# Holder_Accu_Simetric.net
KiCad netlist of a schematic drawn in Altium Designer
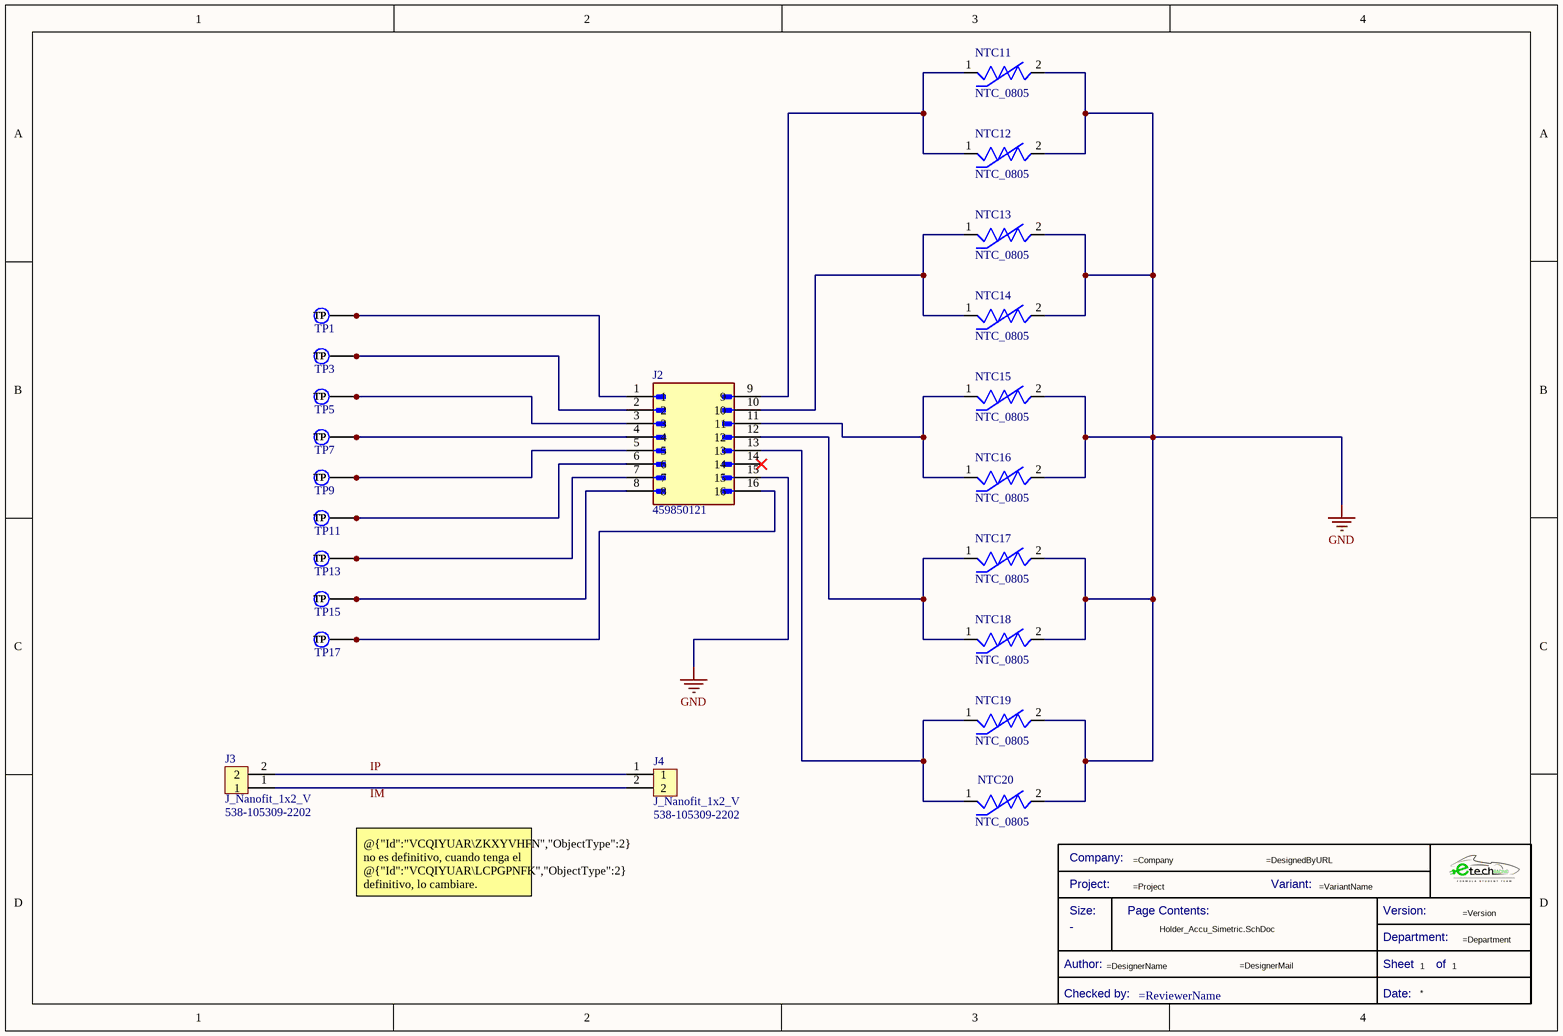
[diagram p0: Holder_Accu_Simetric.SchDoc]

(export (version "E")
  (design (tool "Eeschema 10.0.6"))
  (components
    (comp (ref "*")
      (value "Title Block_template")
      (description "Standard Title Block")
      (fields
        (field (name "SIZE") "-")
        (field (name ".CREATOR") "GP")
        (field (name ".PCBCHECK") "GP")
        (field (name ".SCHCHECK") "GP")
      )
      (libsource (lib "e-Tech_Racing") (part "Title Block_template"))
    )
    (comp (ref "J2")
      (value "459850121")
      (footprint "MOLEX_459850121")
      (libsource (lib "459850121") (part "459850121"))
    )
    (comp (ref "J3")
      (value "J_Nanofit_1x2_V")
      (footprint "J_NanoFit_1X2_V")
      (fields
        (field (name "MANUFACTURER") "Molex")
        (field (name "MANUFACTURER PART NUMBER") "1053092202")
        (field (name "SUPPLIER PART NUMBER 1") "538-105309-2202")
      )
      (libsource (lib "") (part "J_Nanofit_1x2_V_1"))
    )
    (comp (ref "J4")
      (value "J_Nanofit_1x2_V")
      (footprint "J_NanoFit_1X2_V")
      (fields
        (field (name "MANUFACTURER") "Molex")
        (field (name "MANUFACTURER PART NUMBER") "1053092202")
        (field (name "SUPPLIER PART NUMBER 1") "538-105309-2202")
      )
      (libsource (lib "Electromechanical") (part "J_Nanofit_1x2_V"))
    )
    (comp (ref "NTC11")
      (value "NTC_0805")
      (footprint "NTC_0805")
      (description "NTC Thermistor 10k 0805 (2012 Metric)")
      (fields (field (name "MF") "TDK Corporation") (field (name "MP") "NTCG203NH103JTDS"))
      (libsource (lib "yo") (part "NTC_0805"))
    )
    (comp (ref "NTC12")
      (value "NTC_0805")
      (footprint "NTC_0805")
      (description "NTC Thermistor 10k 0805 (2012 Metric)")
      (fields (field (name "MF") "TDK Corporation") (field (name "MP") "NTCG203NH103JTDS"))
      (libsource (lib "yo") (part "NTC_0805"))
    )
    (comp (ref "NTC13")
      (value "NTC_0805")
      (footprint "NTC_0805")
      (description "NTC Thermistor 10k 0805 (2012 Metric)")
      (fields (field (name "MF") "TDK Corporation") (field (name "MP") "NTCG203NH103JTDS"))
      (libsource (lib "yo") (part "NTC_0805"))
    )
    (comp (ref "NTC14")
      (value "NTC_0805")
      (footprint "NTC_0805")
      (description "NTC Thermistor 10k 0805 (2012 Metric)")
      (fields (field (name "MF") "TDK Corporation") (field (name "MP") "NTCG203NH103JTDS"))
      (libsource (lib "yo") (part "NTC_0805"))
    )
    (comp (ref "NTC15")
      (value "NTC_0805")
      (footprint "NTC_0805")
      (description "NTC Thermistor 10k 0805 (2012 Metric)")
      (fields (field (name "MF") "TDK Corporation") (field (name "MP") "NTCG203NH103JTDS"))
      (libsource (lib "yo") (part "NTC_0805"))
    )
    (comp (ref "NTC16")
      (value "NTC_0805")
      (footprint "NTC_0805")
      (description "NTC Thermistor 10k 0805 (2012 Metric)")
      (fields (field (name "MF") "TDK Corporation") (field (name "MP") "NTCG203NH103JTDS"))
      (libsource (lib "yo") (part "NTC_0805"))
    )
    (comp (ref "NTC17")
      (value "NTC_0805")
      (footprint "NTC_0805")
      (description "NTC Thermistor 10k 0805 (2012 Metric)")
      (fields (field (name "MF") "TDK Corporation") (field (name "MP") "NTCG203NH103JTDS"))
      (libsource (lib "yo") (part "NTC_0805"))
    )
    (comp (ref "NTC18")
      (value "NTC_0805")
      (footprint "NTC_0805")
      (description "NTC Thermistor 10k 0805 (2012 Metric)")
      (fields (field (name "MF") "TDK Corporation") (field (name "MP") "NTCG203NH103JTDS"))
      (libsource (lib "yo") (part "NTC_0805"))
    )
    (comp (ref "NTC19")
      (value "NTC_0805")
      (footprint "NTC_0805")
      (description "NTC Thermistor 10k 0805 (2012 Metric)")
      (fields (field (name "MF") "TDK Corporation") (field (name "MP") "NTCG203NH103JTDS"))
      (libsource (lib "yo") (part "NTC_0805"))
    )
    (comp (ref "NTC20")
      (value "NTC_0805")
      (footprint "NTC_0805")
      (description "NTC Thermistor 10k 0805 (2012 Metric)")
      (fields (field (name "MF") "TDK Corporation") (field (name "MP") "NTCG203NH103JTDS"))
      (libsource (lib "yo") (part "NTC_0805"))
    )
    (comp (ref "TP1")
      (value "Test Point")
      (footprint "TESTPOINT_WIDE")
      (description "TestPoint 5x5mm")
      (libsource (lib "e-Tech_Racing") (part "TestPoint_Wide"))
    )
    (comp (ref "TP3")
      (value "Test Point")
      (footprint "TESTPOINT_WIDE")
      (description "TestPoint 5x5mm")
      (libsource (lib "e-Tech_Racing") (part "TestPoint_Wide"))
    )
    (comp (ref "TP5")
      (value "Test Point")
      (footprint "TESTPOINT_WIDE")
      (description "TestPoint 5x5mm")
      (libsource (lib "e-Tech_Racing") (part "TestPoint_Wide"))
    )
    (comp (ref "TP7")
      (value "Test Point")
      (footprint "TESTPOINT_WIDE")
      (description "TestPoint 5x5mm")
      (libsource (lib "e-Tech_Racing") (part "TestPoint_Wide"))
    )
    (comp (ref "TP9")
      (value "Test Point")
      (footprint "TESTPOINT_WIDE")
      (description "TestPoint 5x5mm")
      (libsource (lib "e-Tech_Racing") (part "TestPoint_Wide"))
    )
    (comp (ref "TP11")
      (value "Test Point")
      (footprint "TESTPOINT_WIDE")
      (description "TestPoint 5x5mm")
      (libsource (lib "e-Tech_Racing") (part "TestPoint_Wide"))
    )
    (comp (ref "TP13")
      (value "Test Point")
      (footprint "TESTPOINT_WIDE")
      (description "TestPoint 5x5mm")
      (libsource (lib "e-Tech_Racing") (part "TestPoint_Wide"))
    )
    (comp (ref "TP15")
      (value "Test Point")
      (footprint "TESTPOINT_WIDE")
      (description "TestPoint 5x5mm")
      (libsource (lib "e-Tech_Racing") (part "TestPoint_Wide"))
    )
    (comp (ref "TP17")
      (value "Test Point")
      (footprint "TESTPOINT_WIDE")
      (description "TestPoint 5x5mm")
      (libsource (lib "e-Tech_Racing") (part "TestPoint_Wide"))
    )
  )
  (nets
    (net (code "2") (name "/IP") (class "Default")
      (node (ref "J3") (pin "2") (pinfunction "2_2") (pintype "passive"))
      (node (ref "J4") (pin "1") (pinfunction "1_1") (pintype "passive"))
    )
    (net (code "3") (name "GND") (class "Default")
      (node (ref "J2") (pin "15") (pinfunction "15_15") (pintype "passive"))
      (node (ref "NTC11") (pin "2") (pinfunction "2_2") (pintype "passive"))
      (node (ref "NTC12") (pin "2") (pinfunction "2_2") (pintype "passive"))
      (node (ref "NTC13") (pin "2") (pinfunction "2_2") (pintype "passive"))
      (node (ref "NTC14") (pin "2") (pinfunction "2_2") (pintype "passive"))
      (node (ref "NTC15") (pin "2") (pinfunction "2_2") (pintype "passive"))
      (node (ref "NTC16") (pin "2") (pinfunction "2_2") (pintype "passive"))
      (node (ref "NTC17") (pin "2") (pinfunction "2_2") (pintype "passive"))
      (node (ref "NTC18") (pin "2") (pinfunction "2_2") (pintype "passive"))
      (node (ref "NTC19") (pin "2") (pinfunction "2_2") (pintype "passive"))
      (node (ref "NTC20") (pin "2") (pinfunction "2_2") (pintype "passive"))
    )
    (net (code "4") (name "Net-(J2-Pad9)") (class "Default")
      (node (ref "J2") (pin "9") (pinfunction "9_9") (pintype "passive"))
      (node (ref "NTC11") (pin "1") (pinfunction "1_1") (pintype "passive"))
      (node (ref "NTC12") (pin "1") (pinfunction "1_1") (pintype "passive"))
    )
    (net (code "5") (name "Net-(J2-Pad10)") (class "Default")
      (node (ref "J2") (pin "10") (pinfunction "10_10") (pintype "passive"))
      (node (ref "NTC13") (pin "1") (pinfunction "1_1") (pintype "passive"))
      (node (ref "NTC14") (pin "1") (pinfunction "1_1") (pintype "passive"))
    )
    (net (code "6") (name "Net-(J2-Pad11)") (class "Default")
      (node (ref "J2") (pin "11") (pinfunction "11_11") (pintype "passive"))
      (node (ref "NTC15") (pin "1") (pinfunction "1_1") (pintype "passive"))
      (node (ref "NTC16") (pin "1") (pinfunction "1_1") (pintype "passive"))
    )
    (net (code "7") (name "Net-(J2-Pad12)") (class "Default")
      (node (ref "J2") (pin "12") (pinfunction "12_12") (pintype "passive"))
      (node (ref "NTC17") (pin "1") (pinfunction "1_1") (pintype "passive"))
      (node (ref "NTC18") (pin "1") (pinfunction "1_1") (pintype "passive"))
    )
    (net (code "8") (name "Net-(J2-Pad13)") (class "Default")
      (node (ref "J2") (pin "13") (pinfunction "13_13") (pintype "passive"))
      (node (ref "NTC19") (pin "1") (pinfunction "1_1") (pintype "passive"))
      (node (ref "NTC20") (pin "1") (pinfunction "1_1") (pintype "passive"))
    )
    (net (code "9") (name "Net-(J3-Pad1)") (class "Default")
      (node (ref "J3") (pin "1") (pinfunction "1_1") (pintype "passive"))
      (node (ref "J4") (pin "2") (pinfunction "2_2") (pintype "passive"))
    )
    (net (code "10") (name "Net-(TP1-TP)") (class "Default")
      (node (ref "J2") (pin "1") (pinfunction "1_1") (pintype "passive"))
      (node (ref "TP1") (pin "1") (pinfunction "TP_1") (pintype "passive"))
    )
    (net (code "11") (name "Net-(TP3-TP)") (class "Default")
      (node (ref "J2") (pin "2") (pinfunction "2_2") (pintype "passive"))
      (node (ref "TP3") (pin "1") (pinfunction "TP_1") (pintype "passive"))
    )
    (net (code "12") (name "Net-(TP5-TP)") (class "Default")
      (node (ref "J2") (pin "3") (pinfunction "3_3") (pintype "passive"))
      (node (ref "TP5") (pin "1") (pinfunction "TP_1") (pintype "passive"))
    )
    (net (code "13") (name "Net-(TP7-TP)") (class "Default")
      (node (ref "J2") (pin "4") (pinfunction "4_4") (pintype "passive"))
      (node (ref "TP7") (pin "1") (pinfunction "TP_1") (pintype "passive"))
    )
    (net (code "14") (name "Net-(TP9-TP)") (class "Default")
      (node (ref "J2") (pin "5") (pinfunction "5_5") (pintype "passive"))
      (node (ref "TP9") (pin "1") (pinfunction "TP_1") (pintype "passive"))
    )
    (net (code "15") (name "Net-(TP11-TP)") (class "Default")
      (node (ref "J2") (pin "6") (pinfunction "6_6") (pintype "passive"))
      (node (ref "TP11") (pin "1") (pinfunction "TP_1") (pintype "passive"))
    )
    (net (code "16") (name "Net-(TP13-TP)") (class "Default")
      (node (ref "J2") (pin "7") (pinfunction "7_7") (pintype "passive"))
      (node (ref "TP13") (pin "1") (pinfunction "TP_1") (pintype "passive"))
    )
    (net (code "17") (name "Net-(TP15-TP)") (class "Default")
      (node (ref "J2") (pin "8") (pinfunction "8_8") (pintype "passive"))
      (node (ref "TP15") (pin "1") (pinfunction "TP_1") (pintype "passive"))
    )
    (net (code "18") (name "Net-(TP17-TP)") (class "Default")
      (node (ref "J2") (pin "16") (pinfunction "16_16") (pintype "passive"))
      (node (ref "TP17") (pin "1") (pinfunction "TP_1") (pintype "passive"))
    )
    (net (code "19") (name "unconnected-(J2-Pad14)") (class "Default")
      (node (ref "J2") (pin "14") (pinfunction "14_14") (pintype "passive+no_connect"))
    )
  )
)
